# Main.net
KiCad netlist of a schematic drawn in Altium Designer
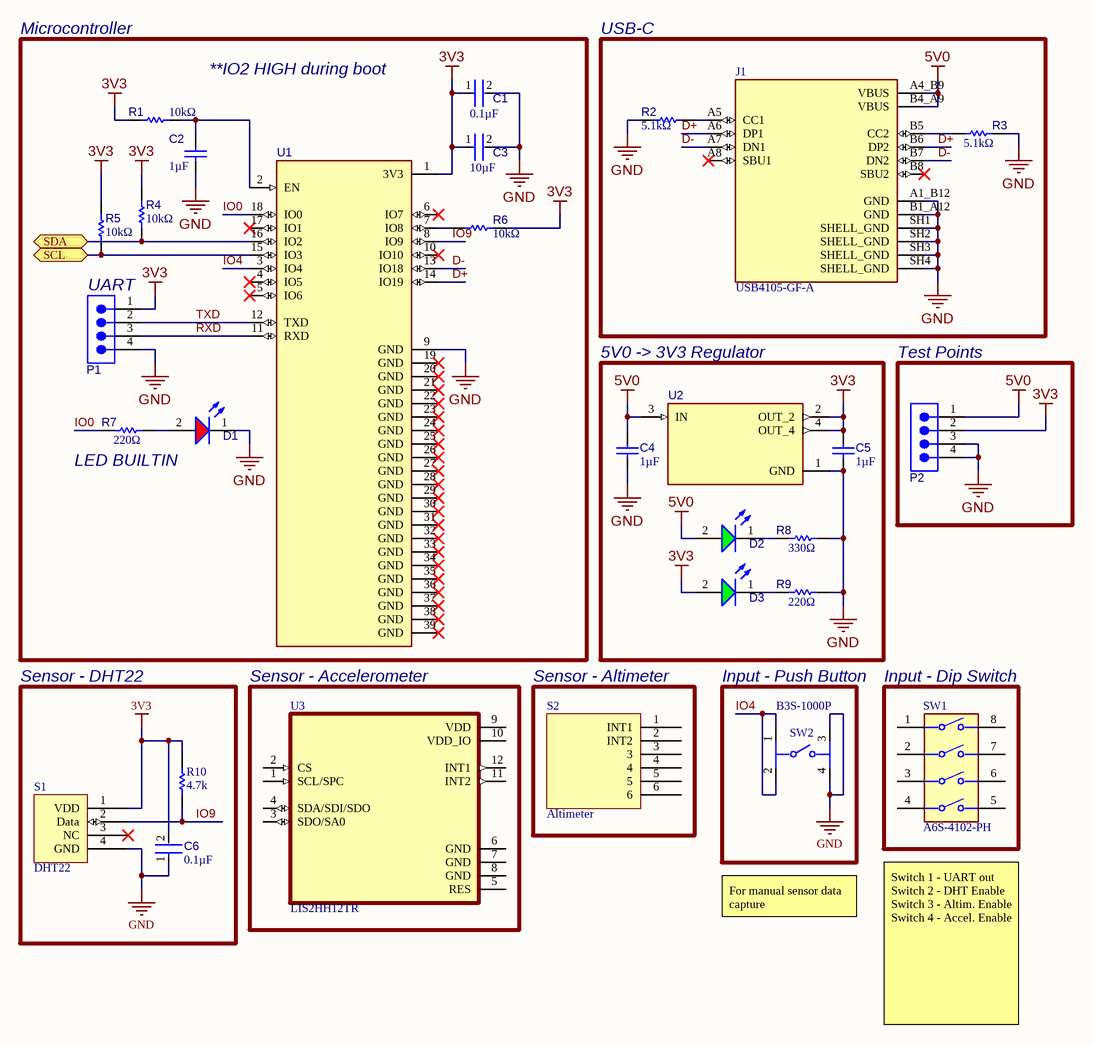
[diagram p0: Main.SchDoc]

(export (version "E")
  (design (tool "Eeschema 10.0.6"))
  (components
    (comp (ref "C1")
      (value "0.1µF")
      (footprint "FP-C1206C-EB-MFG")
      (description "CAP CER 0.1UF 100V X7R 1206")
      (fields
        (field (name "TOLERANCE") "0.1")
        (field (name "OCTOPART") "https://octopart.com/c1206c104k1ractu-kemet-89521")
      )
      (libsource (lib "Altium Content Vault") (part "b4654b650e69147ec39a6b967a45e02"))
    )
    (comp (ref "C2")
      (value "1µF")
      (footprint "CAPC3216X110X50LL20T25")
      (description "Chip Capacitor, 1 uF, +/- 10%, 50 V, -55 to 125 degC, 1206 (3216 Metric), RoHS, Tape and Reel")
      (fields (field (name "MANUFACTURER") "Kemet") (field (name "TOLERANCE") "10%"))
      (libsource (lib "Altium Content Vault") (part "CAP-NP-2"))
    )
    (comp (ref "C3")
      (value "10µF")
      (footprint "FP-GRM31C-0_2-e0_3_0_8-MFG")
      (description "Chip Multilayer Ceramic Capacitors for General Purpose, 1206, 10uF, X7R, 15%, 10%, 25V")
      (fields (field (name "TOLERANCE") "10%") (field (name "VOLTAGE") "25V"))
      (libsource (lib "Altium Content Vault") (part "02cd4be3c70576c341d710602a673aa"))
    )
    (comp (ref "C4")
      (value "1µF")
      (footprint "CAPC3216X110X50LL20T25")
      (description "Chip Capacitor, 1 uF, +/- 10%, 50 V, -55 to 125 degC, 1206 (3216 Metric), RoHS, Tape and Reel")
      (fields (field (name "MANUFACTURER") "Kemet") (field (name "TOLERANCE") "10%"))
      (libsource (lib "Altium Content Vault") (part "CAP-NP-2"))
    )
    (comp (ref "C5")
      (value "1µF")
      (footprint "CAPC3216X110X50LL20T25")
      (description "Chip Capacitor, 1 uF, +/- 10%, 50 V, -55 to 125 degC, 1206 (3216 Metric), RoHS, Tape and Reel")
      (fields (field (name "MANUFACTURER") "Kemet") (field (name "TOLERANCE") "10%"))
      (libsource (lib "Altium Content Vault") (part "CAP-NP-2"))
    )
    (comp (ref "C6")
      (value "0.1µF")
      (footprint "FP-C1206C-EB-MFG")
      (description "CAP CER 0.1UF 100V X7R 1206")
      (fields
        (field (name "TOLERANCE") "0.1")
        (field (name "OCTOPART") "https://octopart.com/c1206c104k1ractu-kemet-89521")
      )
      (libsource (lib "Altium Content Vault") (part "b4654b650e69147ec39a6b967a45e02"))
    )
    (comp (ref "D1")
      (value "150120SS75000")
      (footprint "WL-SMCW_1206_150120xx75000")
      (description "Led, Red, 630 Nm, 1.9 V, 30 Ma, 60 Mcd Rohs Compliant: Yes")
      (libsource (lib "Altium Content Vault") (part "LED_Red_2A-1K"))
    )
    (comp (ref "D2")
      (value "150120GS75000")
      (footprint "WL-SMCW_1206_150120xx75000")
      (description "WL-SMCW SMT Mono-Color Chip LED Waterclear")
      (libsource (lib "Altium Content Vault") (part "LED_Green_2A-1K"))
    )
    (comp (ref "D3")
      (value "150120GS75000")
      (footprint "WL-SMCW_1206_150120xx75000")
      (description "WL-SMCW SMT Mono-Color Chip LED Waterclear")
      (libsource (lib "Altium Content Vault") (part "LED_Green_2A-1K"))
    )
    (comp (ref "J1")
      (value "USB4105-GF-A")
      (footprint "GCT_USB4105-GF-A")
      (fields (field (name "MF") "{'manufacturer': u'GCT'}"))
      (libsource (lib "USB4105-GF-A") (part "USB4105-GF-A"))
    )
    (comp (ref "P1")
      (value "61300411121")
      (footprint "61300411121")
      (description "WR-PHD Pin Header, THT, Vertical, pitch 2.54mm, 1 Row, 4P")
      (fields (field (name "MANUFACTURER") "Wurth Elektronik"))
      (libsource (lib "Altium_WR-PHD_rev24a") (part "61300411121"))
    )
    (comp (ref "P2")
      (value "61300411121")
      (footprint "61300411121")
      (description "WR-PHD Pin Header, THT, Vertical, pitch 2.54mm, 1 Row, 4P")
      (fields (field (name "MANUFACTURER") "Wurth Elektronik"))
      (libsource (lib "Altium_WR-PHD_rev24a") (part "61300411121"))
    )
    (comp (ref "R1")
      (value "10kΩ")
      (footprint "RESC3216X70X50LL20T25")
      (fields (field (name "MANUFACTURER") "Panasonic") (field (name "PART NUMBER") "ERA8AEB103V"))
      (libsource (lib "Altium Content Vault") (part "RES"))
    )
    (comp (ref "R2")
      (value "5.1kΩ")
      (footprint "RESC3216X70X50NL05T20")
      (fields (field (name "PART NUMBER") "ERJ-8ENF5101V") (field (name "MANUFACTURER") "Panasonic"))
      (libsource (lib "Altium Content Vault") (part "RES"))
    )
    (comp (ref "R3")
      (value "5.1kΩ")
      (footprint "RESC3216X70X50NL05T20")
      (fields (field (name "PART NUMBER") "ERJ-8ENF5101V") (field (name "MANUFACTURER") "Panasonic"))
      (libsource (lib "Altium Content Vault") (part "RES"))
    )
    (comp (ref "R4")
      (value "10kΩ")
      (footprint "RESC3216X70X50LL20T25")
      (fields (field (name "MANUFACTURER") "Panasonic") (field (name "PART NUMBER") "ERA8AEB103V"))
      (libsource (lib "Altium Content Vault") (part "RES"))
    )
    (comp (ref "R5")
      (value "10kΩ")
      (footprint "RESC3216X70X50LL20T25")
      (fields (field (name "MANUFACTURER") "Panasonic") (field (name "PART NUMBER") "ERA8AEB103V"))
      (libsource (lib "Altium Content Vault") (part "RES"))
    )
    (comp (ref "R6")
      (value "10kΩ")
      (footprint "RESC3216X70X50LL20T25")
      (fields (field (name "MANUFACTURER") "Panasonic") (field (name "PART NUMBER") "ERA8AEB103V"))
      (libsource (lib "Altium Content Vault") (part "RES"))
    )
    (comp (ref "R7")
      (value "220Ω")
      (footprint "RESC3216X70X50ML20T25")
      (fields (field (name "PART NUMBER") "ERA8AEB221V") (field (name "MANUFACTURER") "Panasonic"))
      (libsource (lib "Altium Content Vault") (part "RES"))
    )
    (comp (ref "R8")
      (value "330Ω")
      (footprint "RESC3216X70X50NL05T20")
      (fields (field (name "MANUFACTURER") "Panasonic") (field (name "PART NUMBER") "ERJ-8GEYJ331V"))
      (libsource (lib "Altium Content Vault") (part "RES"))
    )
    (comp (ref "R9")
      (value "220Ω")
      (footprint "RESC3216X70X50ML20T25")
      (fields (field (name "PART NUMBER") "ERA8AEB221V") (field (name "MANUFACTURER") "Panasonic"))
      (libsource (lib "Altium Content Vault") (part "RES"))
    )
    (comp (ref "R10")
      (value "4.7k")
      (footprint "RESC3216X70X50LL05T20")
      (fields (field (name "PART NUMBER") "ERJ8ENF4701V") (field (name "MANUFACTURER") "Panasonic"))
      (libsource (lib "Altium Content Vault") (part "RES"))
    )
    (comp (ref "S1")
      (value "DHT22")
      (footprint "DHT22_Footprint")
      (description "DHT22 Sensor")
      (libsource (lib "DHT22-Library") (part "DHT22"))
    )
    (comp (ref "S2")
      (value "Altimeter")
      (footprint "altimeter_footprint")
      (libsource (lib "Altimeter-Library") (part "Altimeter"))
    )
    (comp (ref "SW1")
      (value "A6S-4102-PH")
      (footprint "FP-A6S-4102-PH-MFG")
      (description "SWITCH SLIDE DIP SPST 25MA 24V")
      (libsource (lib "Altium Content Vault") (part "ebab07a280aa026a71d790bff2a9996"))
    )
    (comp (ref "SW2")
      (value "B3S-1000P")
      (footprint "FP-B3S-1000P-MFG")
      (description "SWITCH TACTILE SPST-NO 0.05A 24V")
      (libsource (lib "Altium Content Vault") (part "b8895f3f4cefb76e1819d2863dba89b"))
    )
    (comp (ref "U1")
      (value "ESP32-C3-WROOM-02-N4")
      (footprint "MODULE_ESP32-C3-WROOM-02-H4")
      (fields (field (name "MF") "Espressif Systems"))
      (libsource (lib "ESP32-C3-WROOM-02-N4") (part "ESP32-C3-WROOM-02-N4"))
    )
    (comp (ref "U2")
      (value "TLV1117LV33DCYR")
      (footprint "VREG_TLV1117LV33DCYR")
      (description "1-A, low-dropout voltage regulator")
      (fields (field (name "DIGI-KEY_PART_NUMBER") "296-28778-2-ND") (field (name "MF") "Texas Instruments"))
      (libsource (lib "TLV1117LV33DCYR") (part "TLV1117LV33DCYR"))
    )
    (comp (ref "U3")
      (value "LIS2HH12TR")
      (footprint "PQFN50P200X200X100-12N")
      (description "Accelerometer X, Y, Z Axis Â±2g, 4g, 8g 5Hz ~ 400Hz 12-LGA _2x2_")
      (fields (field (name "MF") "STMicroelectronics"))
      (libsource (lib "LIS2HH12TR-Library") (part "LIS2HH12TR"))
    )
  )
  (nets
    (net (code "1") (name "/D+") (class "Default")
      (node (ref "J1") (pin "A6") (pinfunction "DP1_A6") (pintype "bidirectional"))
      (node (ref "J1") (pin "B6") (pinfunction "DP2_B6") (pintype "bidirectional"))
      (node (ref "U1") (pin "14") (pinfunction "IO19_14") (pintype "bidirectional"))
    )
    (net (code "2") (name "/D-") (class "Default")
      (node (ref "J1") (pin "A7") (pinfunction "DN1_A7") (pintype "bidirectional"))
      (node (ref "J1") (pin "B7") (pinfunction "DN2_B7") (pintype "bidirectional"))
      (node (ref "U1") (pin "13") (pinfunction "IO18_13") (pintype "bidirectional"))
    )
    (net (code "3") (name "/IO0") (class "Default")
      (node (ref "R7") (pin "1") (pinfunction "1_1") (pintype "passive"))
      (node (ref "U1") (pin "18") (pinfunction "IO0_18") (pintype "bidirectional"))
    )
    (net (code "4") (name "/IO4") (class "Default")
      (node (ref "SW2") (pin "1") (pinfunction "1_1") (pintype "passive"))
      (node (ref "SW2") (pin "2") (pinfunction "2_2") (pintype "passive"))
      (node (ref "U1") (pin "3") (pinfunction "IO4_3") (pintype "bidirectional"))
    )
    (net (code "5") (name "/IO9") (class "Default")
      (node (ref "R10") (pin "1") (pinfunction "1_1") (pintype "passive"))
      (node (ref "S1") (pin "2") (pinfunction "Data_2") (pintype "bidirectional"))
      (node (ref "U1") (pin "8") (pinfunction "IO9_8") (pintype "bidirectional"))
    )
    (net (code "6") (name "/RXD") (class "Default")
      (node (ref "P1") (pin "3") (pinfunction "3_3") (pintype "passive"))
      (node (ref "U1") (pin "11") (pinfunction "RXD_11") (pintype "bidirectional"))
    )
    (net (code "7") (name "/SCL") (class "Default")
      (node (ref "R5") (pin "1") (pinfunction "1_1") (pintype "passive"))
      (node (ref "U1") (pin "15") (pinfunction "IO3_15") (pintype "bidirectional"))
    )
    (net (code "8") (name "/SDA") (class "Default")
      (node (ref "R4") (pin "1") (pinfunction "1_1") (pintype "passive"))
      (node (ref "U1") (pin "16") (pinfunction "IO2_16") (pintype "bidirectional"))
    )
    (net (code "9") (name "/TXD") (class "Default")
      (node (ref "P1") (pin "2") (pinfunction "2_2") (pintype "passive"))
      (node (ref "U1") (pin "12") (pinfunction "TXD_12") (pintype "bidirectional"))
    )
    (net (code "10") (name "3V3") (class "Default")
      (node (ref "C1") (pin "1") (pinfunction "1_1") (pintype "passive"))
      (node (ref "C3") (pin "1") (pinfunction "1_1") (pintype "passive"))
      (node (ref "C5") (pin "2") (pinfunction "2_2") (pintype "passive"))
      (node (ref "C6") (pin "2") (pinfunction "2_2") (pintype "passive"))
      (node (ref "D3") (pin "2") (pinfunction "A_2") (pintype "passive"))
      (node (ref "P1") (pin "1") (pinfunction "1_1") (pintype "passive"))
      (node (ref "P2") (pin "2") (pinfunction "2_2") (pintype "passive"))
      (node (ref "R1") (pin "1") (pinfunction "1_1") (pintype "passive"))
      (node (ref "R10") (pin "2") (pinfunction "2_2") (pintype "passive"))
      (node (ref "R4") (pin "2") (pinfunction "2_2") (pintype "passive"))
      (node (ref "R5") (pin "2") (pinfunction "2_2") (pintype "passive"))
      (node (ref "R6") (pin "2") (pinfunction "2_2") (pintype "passive"))
      (node (ref "S1") (pin "1") (pinfunction "VDD_1") (pintype "power_in"))
      (node (ref "U1") (pin "1") (pinfunction "3V3_1") (pintype "power_in"))
      (node (ref "U2") (pin "2") (pinfunction "OUT_2_2") (pintype "output"))
      (node (ref "U2") (pin "4") (pinfunction "OUT_4_4") (pintype "output"))
    )
    (net (code "11") (name "5V0") (class "Default")
      (node (ref "C4") (pin "2") (pinfunction "2_2") (pintype "passive"))
      (node (ref "D2") (pin "2") (pinfunction "A_2") (pintype "passive"))
      (node (ref "J1") (pin "A4_B9") (pinfunction "VBUS_A4_B9") (pintype "power_in"))
      (node (ref "J1") (pin "B4_A9") (pinfunction "VBUS_B4_A9") (pintype "power_in"))
      (node (ref "P2") (pin "1") (pinfunction "1_1") (pintype "passive"))
      (node (ref "U2") (pin "3") (pinfunction "IN_3") (pintype "input"))
    )
    (net (code "12") (name "GND") (class "Default")
      (node (ref "C1") (pin "2") (pinfunction "2_2") (pintype "passive"))
      (node (ref "C2") (pin "1") (pinfunction "1_1") (pintype "passive"))
      (node (ref "C3") (pin "2") (pinfunction "2_2") (pintype "passive"))
      (node (ref "C4") (pin "1") (pinfunction "1_1") (pintype "passive"))
      (node (ref "C5") (pin "1") (pinfunction "1_1") (pintype "passive"))
      (node (ref "C6") (pin "1") (pinfunction "1_1") (pintype "passive"))
      (node (ref "D1") (pin "1") (pinfunction "K_1") (pintype "passive"))
      (node (ref "J1") (pin "A1_B12") (pinfunction "GND_A1_B12") (pintype "power_in"))
      (node (ref "J1") (pin "B1_A12") (pinfunction "GND_B1_A12") (pintype "power_in"))
      (node (ref "J1") (pin "SH1") (pinfunction "SHELL_GND_SH1") (pintype "power_in"))
      (node (ref "J1") (pin "SH2") (pinfunction "SHELL_GND_SH2") (pintype "power_in"))
      (node (ref "J1") (pin "SH3") (pinfunction "SHELL_GND_SH3") (pintype "power_in"))
      (node (ref "J1") (pin "SH4") (pinfunction "SHELL_GND_SH4") (pintype "power_in"))
      (node (ref "P1") (pin "4") (pinfunction "4_4") (pintype "passive"))
      (node (ref "P2") (pin "3") (pinfunction "3_3") (pintype "passive"))
      (node (ref "P2") (pin "4") (pinfunction "4_4") (pintype "passive"))
      (node (ref "R2") (pin "1") (pinfunction "1_1") (pintype "passive"))
      (node (ref "R3") (pin "2") (pinfunction "2_2") (pintype "passive"))
      (node (ref "R8") (pin "2") (pinfunction "2_2") (pintype "passive"))
      (node (ref "R9") (pin "2") (pinfunction "2_2") (pintype "passive"))
      (node (ref "S1") (pin "4") (pinfunction "GND_4") (pintype "passive"))
      (node (ref "SW2") (pin "3") (pinfunction "3_3") (pintype "passive"))
      (node (ref "SW2") (pin "4") (pinfunction "4_4") (pintype "passive"))
      (node (ref "U1") (pin "9") (pinfunction "GND_9") (pintype "power_in"))
      (node (ref "U2") (pin "1") (pinfunction "GND_1") (pintype "power_in"))
    )
    (net (code "13") (name "Net-(D1-A)") (class "Default")
      (node (ref "D1") (pin "2") (pinfunction "A_2") (pintype "passive"))
      (node (ref "R7") (pin "2") (pinfunction "2_2") (pintype "passive"))
    )
    (net (code "14") (name "Net-(D2-K)") (class "Default")
      (node (ref "D2") (pin "1") (pinfunction "K_1") (pintype "passive"))
      (node (ref "R8") (pin "1") (pinfunction "1_1") (pintype "passive"))
    )
    (net (code "15") (name "Net-(D3-K)") (class "Default")
      (node (ref "D3") (pin "1") (pinfunction "K_1") (pintype "passive"))
      (node (ref "R9") (pin "1") (pinfunction "1_1") (pintype "passive"))
    )
    (net (code "16") (name "Net-(J1-CC1)") (class "Default")
      (node (ref "J1") (pin "A5") (pinfunction "CC1_A5") (pintype "bidirectional"))
      (node (ref "R2") (pin "2") (pinfunction "2_2") (pintype "passive"))
    )
    (net (code "17") (name "Net-(J1-CC2)") (class "Default")
      (node (ref "J1") (pin "B5") (pinfunction "CC2_B5") (pintype "bidirectional"))
      (node (ref "R3") (pin "1") (pinfunction "1_1") (pintype "passive"))
    )
    (net (code "18") (name "Net-(U1-EN)") (class "Default")
      (node (ref "C2") (pin "2") (pinfunction "2_2") (pintype "passive"))
      (node (ref "R1") (pin "2") (pinfunction "2_2") (pintype "passive"))
      (node (ref "U1") (pin "2") (pinfunction "EN_2") (pintype "input"))
    )
    (net (code "19") (name "Net-(U1-IO8)") (class "Default")
      (node (ref "R6") (pin "1") (pinfunction "1_1") (pintype "passive"))
      (node (ref "U1") (pin "7") (pinfunction "IO8_7") (pintype "bidirectional"))
    )
    (net (code "20") (name "unconnected-(J1-SBU1-PadA8)") (class "Default")
      (node (ref "J1") (pin "A8") (pinfunction "SBU1_A8") (pintype "bidirectional+no_connect"))
    )
    (net (code "21") (name "unconnected-(J1-SBU2-PadB8)") (class "Default")
      (node (ref "J1") (pin "B8") (pinfunction "SBU2_B8") (pintype "bidirectional+no_connect"))
    )
    (net (code "22") (name "unconnected-(S1-NC-Pad3)") (class "Default")
      (node (ref "S1") (pin "3") (pinfunction "NC_3") (pintype "passive+no_connect"))
    )
    (net (code "23") (name "unconnected-(S2-INT1-Pad1)") (class "Default")
      (node (ref "S2") (pin "1") (pinfunction "INT1_1") (pintype "passive"))
    )
    (net (code "24") (name "unconnected-(S2-INT2-Pad2)") (class "Default")
      (node (ref "S2") (pin "2") (pinfunction "INT2_2") (pintype "passive"))
    )
    (net (code "25") (name "unconnected-(S2-Pad3)") (class "Default")
      (node (ref "S2") (pin "3") (pinfunction "3_3") (pintype "passive"))
    )
    (net (code "26") (name "unconnected-(S2-Pad4)") (class "Default")
      (node (ref "S2") (pin "4") (pinfunction "4_4") (pintype "passive"))
    )
    (net (code "27") (name "unconnected-(S2-Pad5)") (class "Default")
      (node (ref "S2") (pin "5") (pinfunction "5_5") (pintype "passive"))
    )
    (net (code "28") (name "unconnected-(S2-Pad6)") (class "Default")
      (node (ref "S2") (pin "6") (pinfunction "6_6") (pintype "passive"))
    )
    (net (code "29") (name "unconnected-(SW1-Pad1)") (class "Default")
      (node (ref "SW1") (pin "1") (pinfunction "1_1") (pintype "passive"))
    )
    (net (code "30") (name "unconnected-(SW1-Pad2)") (class "Default")
      (node (ref "SW1") (pin "2") (pinfunction "2_2") (pintype "passive"))
    )
    (net (code "31") (name "unconnected-(SW1-Pad3)") (class "Default")
      (node (ref "SW1") (pin "3") (pinfunction "3_3") (pintype "passive"))
    )
    (net (code "32") (name "unconnected-(SW1-Pad4)") (class "Default")
      (node (ref "SW1") (pin "4") (pinfunction "4_4") (pintype "passive"))
    )
    (net (code "33") (name "unconnected-(SW1-Pad5)") (class "Default")
      (node (ref "SW1") (pin "5") (pinfunction "5_5") (pintype "passive"))
    )
    (net (code "34") (name "unconnected-(SW1-Pad6)") (class "Default")
      (node (ref "SW1") (pin "6") (pinfunction "6_6") (pintype "passive"))
    )
    (net (code "35") (name "unconnected-(SW1-Pad7)") (class "Default")
      (node (ref "SW1") (pin "7") (pinfunction "7_7") (pintype "passive"))
    )
    (net (code "36") (name "unconnected-(SW1-Pad8)") (class "Default")
      (node (ref "SW1") (pin "8") (pinfunction "8_8") (pintype "passive"))
    )
    (net (code "37") (name "unconnected-(U1-GND-Pad19)") (class "Default")
      (node (ref "U1") (pin "19") (pinfunction "GND_19") (pintype "power_in+no_connect"))
    )
    (net (code "38") (name "unconnected-(U1-GND-Pad20)") (class "Default")
      (node (ref "U1") (pin "20") (pinfunction "GND_20") (pintype "power_in+no_connect"))
    )
    (net (code "39") (name "unconnected-(U1-GND-Pad21)") (class "Default")
      (node (ref "U1") (pin "21") (pinfunction "GND_21") (pintype "power_in+no_connect"))
    )
    (net (code "40") (name "unconnected-(U1-GND-Pad22)") (class "Default")
      (node (ref "U1") (pin "22") (pinfunction "GND_22") (pintype "power_in+no_connect"))
    )
    (net (code "41") (name "unconnected-(U1-GND-Pad23)") (class "Default")
      (node (ref "U1") (pin "23") (pinfunction "GND_23") (pintype "power_in+no_connect"))
    )
    (net (code "42") (name "unconnected-(U1-GND-Pad24)") (class "Default")
      (node (ref "U1") (pin "24") (pinfunction "GND_24") (pintype "power_in+no_connect"))
    )
    (net (code "43") (name "unconnected-(U1-GND-Pad25)") (class "Default")
      (node (ref "U1") (pin "25") (pinfunction "GND_25") (pintype "power_in+no_connect"))
    )
    (net (code "44") (name "unconnected-(U1-GND-Pad26)") (class "Default")
      (node (ref "U1") (pin "26") (pinfunction "GND_26") (pintype "power_in+no_connect"))
    )
    (net (code "45") (name "unconnected-(U1-GND-Pad27)") (class "Default")
      (node (ref "U1") (pin "27") (pinfunction "GND_27") (pintype "power_in+no_connect"))
    )
    (net (code "46") (name "unconnected-(U1-GND-Pad28)") (class "Default")
      (node (ref "U1") (pin "28") (pinfunction "GND_28") (pintype "power_in+no_connect"))
    )
    (net (code "47") (name "unconnected-(U1-GND-Pad29)") (class "Default")
      (node (ref "U1") (pin "29") (pinfunction "GND_29") (pintype "power_in+no_connect"))
    )
    (net (code "48") (name "unconnected-(U1-GND-Pad30)") (class "Default")
      (node (ref "U1") (pin "30") (pinfunction "GND_30") (pintype "power_in+no_connect"))
    )
    (net (code "49") (name "unconnected-(U1-GND-Pad31)") (class "Default")
      (node (ref "U1") (pin "31") (pinfunction "GND_31") (pintype "power_in+no_connect"))
    )
    (net (code "50") (name "unconnected-(U1-GND-Pad32)") (class "Default")
      (node (ref "U1") (pin "32") (pinfunction "GND_32") (pintype "power_in+no_connect"))
    )
    (net (code "51") (name "unconnected-(U1-GND-Pad33)") (class "Default")
      (node (ref "U1") (pin "33") (pinfunction "GND_33") (pintype "power_in+no_connect"))
    )
    (net (code "52") (name "unconnected-(U1-GND-Pad34)") (class "Default")
      (node (ref "U1") (pin "34") (pinfunction "GND_34") (pintype "power_in+no_connect"))
    )
    (net (code "53") (name "unconnected-(U1-GND-Pad35)") (class "Default")
      (node (ref "U1") (pin "35") (pinfunction "GND_35") (pintype "power_in+no_connect"))
    )
    (net (code "54") (name "unconnected-(U1-GND-Pad36)") (class "Default")
      (node (ref "U1") (pin "36") (pinfunction "GND_36") (pintype "power_in+no_connect"))
    )
    (net (code "55") (name "unconnected-(U1-GND-Pad37)") (class "Default")
      (node (ref "U1") (pin "37") (pinfunction "GND_37") (pintype "power_in+no_connect"))
    )
    (net (code "56") (name "unconnected-(U1-GND-Pad38)") (class "Default")
      (node (ref "U1") (pin "38") (pinfunction "GND_38") (pintype "power_in+no_connect"))
    )
    (net (code "57") (name "unconnected-(U1-GND-Pad39)") (class "Default")
      (node (ref "U1") (pin "39") (pinfunction "GND_39") (pintype "power_in+no_connect"))
    )
    (net (code "58") (name "unconnected-(U1-IO1-Pad17)") (class "Default")
      (node (ref "U1") (pin "17") (pinfunction "IO1_17") (pintype "bidirectional+no_connect"))
    )
    (net (code "59") (name "unconnected-(U1-IO5-Pad4)") (class "Default")
      (node (ref "U1") (pin "4") (pinfunction "IO5_4") (pintype "bidirectional+no_connect"))
    )
    (net (code "60") (name "unconnected-(U1-IO6-Pad5)") (class "Default")
      (node (ref "U1") (pin "5") (pinfunction "IO6_5") (pintype "bidirectional+no_connect"))
    )
    (net (code "61") (name "unconnected-(U1-IO7-Pad6)") (class "Default")
      (node (ref "U1") (pin "6") (pinfunction "IO7_6") (pintype "bidirectional+no_connect"))
    )
    (net (code "62") (name "unconnected-(U1-IO10-Pad10)") (class "Default")
      (node (ref "U1") (pin "10") (pinfunction "IO10_10") (pintype "bidirectional+no_connect"))
    )
    (net (code "63") (name "unconnected-(U3-CS-Pad2)") (class "Default")
      (node (ref "U3") (pin "2") (pinfunction "CS_2") (pintype "input"))
    )
    (net (code "64") (name "unconnected-(U3-GND-Pad6)") (class "Default")
      (node (ref "U3") (pin "6") (pinfunction "GND_6") (pintype "power_in"))
    )
    (net (code "65") (name "unconnected-(U3-GND-Pad7)") (class "Default")
      (node (ref "U3") (pin "7") (pinfunction "GND_7") (pintype "power_in"))
    )
    (net (code "66") (name "unconnected-(U3-GND-Pad8)") (class "Default")
      (node (ref "U3") (pin "8") (pinfunction "GND_8") (pintype "power_in"))
    )
    (net (code "67") (name "unconnected-(U3-INT1-Pad12)") (class "Default")
      (node (ref "U3") (pin "12") (pinfunction "INT1_12") (pintype "output"))
    )
    (net (code "68") (name "unconnected-(U3-INT2-Pad11)") (class "Default")
      (node (ref "U3") (pin "11") (pinfunction "INT2_11") (pintype "output"))
    )
    (net (code "69") (name "unconnected-(U3-RES-Pad5)") (class "Default")
      (node (ref "U3") (pin "5") (pinfunction "RES_5") (pintype "power_in"))
    )
    (net (code "70") (name "unconnected-(U3-SCL{slash}SPC-Pad1)") (class "Default")
      (node (ref "U3") (pin "1") (pinfunction "SCL/SPC_1") (pintype "input"))
    )
    (net (code "71") (name "unconnected-(U3-SDA{slash}SDI{slash}SDO-Pad4)") (class "Default")
      (node (ref "U3") (pin "4") (pinfunction "SDA/SDI/SDO_4") (pintype "bidirectional"))
    )
    (net (code "72") (name "unconnected-(U3-SDO{slash}SA0-Pad3)") (class "Default")
      (node (ref "U3") (pin "3") (pinfunction "SDO/SA0_3") (pintype "bidirectional"))
    )
    (net (code "73") (name "unconnected-(U3-VDD-Pad9)") (class "Default")
      (node (ref "U3") (pin "9") (pinfunction "VDD_9") (pintype "power_in"))
    )
    (net (code "74") (name "unconnected-(U3-VDD_IO-Pad10)") (class "Default")
      (node (ref "U3") (pin "10") (pinfunction "VDD_IO_10") (pintype "power_in"))
    )
  )
)
